# Triangulator-LM358.net
KiCad netlist of a schematic drawn in EAGLE
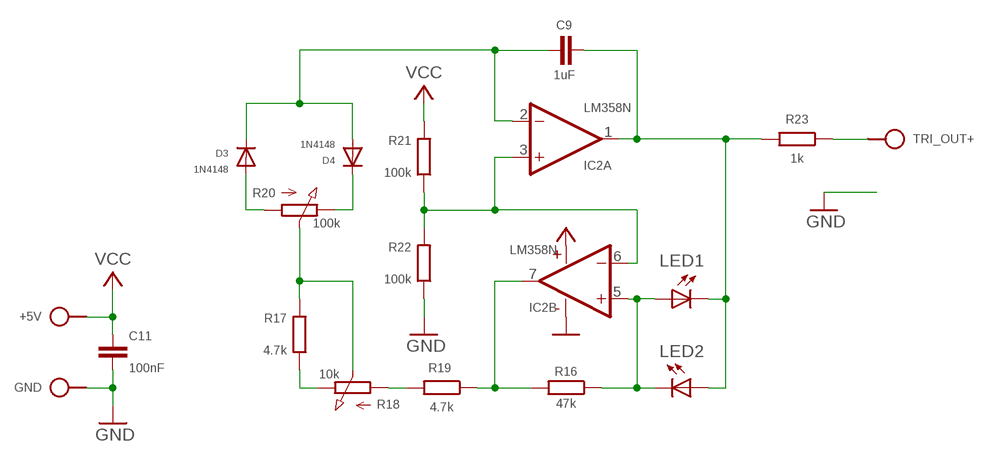
[diagram p0: schematic, sheet 1]

(export (version "E")
  (design (tool "Eeschema 10.0.6"))
  (components
    (comp (ref "+5V")
      (value "VCC")
      (footprint "eagle-import:SPAD")
      (libsource (lib "eagle-import") (part "SPAD"))
    )
    (comp (ref "C9")
      (value "1uF")
      (footprint "eagle-import:C050-020X036_V")
      (libsource (lib "eagle-import") (part "C050-020X036/V"))
    )
    (comp (ref "C11")
      (value "100nF")
      (footprint "eagle-import:C050-020X036")
      (libsource (lib "eagle-import") (part "C050-020X036"))
    )
    (comp (ref "D3")
      (value "1N4148")
      (footprint "eagle-import:DO34-5V")
      (libsource (lib "eagle-import") (part "1N414834-5V"))
    )
    (comp (ref "D4")
      (value "1N4148")
      (footprint "eagle-import:DO34-5V")
      (libsource (lib "eagle-import") (part "1N414834-5V"))
    )
    (comp (ref "GND")
      (value "GND")
      (footprint "eagle-import:SPAD")
      (libsource (lib "eagle-import") (part "SPAD"))
    )
    (comp (ref "IC2")
      (value "LM358N")
      (footprint "eagle-import:DIL08")
      (libsource (lib "eagle-import") (part "LM358N"))
    )
    (comp (ref "LED1")
      (value "LED3MM")
      (footprint "eagle-import:LED3MM")
      (libsource (lib "eagle-import") (part "LED3MM"))
    )
    (comp (ref "LED2")
      (value "LED3MM")
      (footprint "eagle-import:LED3MM")
      (libsource (lib "eagle-import") (part "LED3MM"))
    )
    (comp (ref "R16")
      (value "47k")
      (footprint "eagle-import:0202_7-V")
      (libsource (lib "eagle-import") (part "R0202/7-V"))
    )
    (comp (ref "R17")
      (value "4.7k")
      (footprint "eagle-import:0202_7")
      (libsource (lib "eagle-import") (part "R0202/7"))
    )
    (comp (ref "R18")
      (value "10k")
      (footprint "eagle-import:POT")
      (libsource (lib "eagle-import") (part "POT"))
    )
    (comp (ref "R19")
      (value "4.7k")
      (footprint "eagle-import:0202_7-V")
      (libsource (lib "eagle-import") (part "R0202/7-V"))
    )
    (comp (ref "R20")
      (value "100k")
      (footprint "eagle-import:POT")
      (libsource (lib "eagle-import") (part "POT"))
    )
    (comp (ref "R21")
      (value "100k")
      (footprint "eagle-import:0202_7-V")
      (libsource (lib "eagle-import") (part "R0202/7-V"))
    )
    (comp (ref "R22")
      (value "100k")
      (footprint "eagle-import:0202_7-V")
      (libsource (lib "eagle-import") (part "R0202/7-V"))
    )
    (comp (ref "R23")
      (value "1k")
      (footprint "eagle-import:0202_5")
      (libsource (lib "eagle-import") (part "R0202/5"))
    )
    (comp (ref "TRI_OUT+")
      (value "TRIANGLE")
      (footprint "eagle-import:SPAD")
      (libsource (lib "eagle-import") (part "SPAD"))
    )
  )
  (nets
    (net (code "1") (name "GND") (class "Default")
      (node (ref "C11") (pin "2") (pinfunction "2_2") (pintype "passive"))
      (node (ref "GND") (pin "1") (pinfunction "P$1_1") (pintype "bidirectional"))
      (node (ref "IC2") (pin "4") (pinfunction "V-_4") (pintype "power_in"))
      (node (ref "R22") (pin "1") (pinfunction "1_1") (pintype "passive"))
    )
    (net (code "2") (name "Net-(IC2A-+IN)") (class "Default")
      (node (ref "IC2") (pin "3") (pinfunction "+IN_3") (pintype "input"))
      (node (ref "IC2") (pin "6") (pinfunction "-IN_6") (pintype "input"))
      (node (ref "R21") (pin "1") (pinfunction "1_1") (pintype "passive"))
      (node (ref "R22") (pin "2") (pinfunction "2_2") (pintype "passive"))
    )
    (net (code "3") (name "Net-(IC2A--IN)") (class "Default")
      (node (ref "C9") (pin "1") (pinfunction "1_1") (pintype "passive"))
      (node (ref "D3") (pin "C") (pinfunction "C_C") (pintype "passive"))
      (node (ref "D4") (pin "A") (pinfunction "A_A") (pintype "passive"))
      (node (ref "IC2") (pin "2") (pinfunction "-IN_2") (pintype "input"))
    )
    (net (code "4") (name "Net-(IC2A-OUT)") (class "Default")
      (node (ref "C9") (pin "2") (pinfunction "2_2") (pintype "passive"))
      (node (ref "IC2") (pin "1") (pinfunction "OUT_1") (pintype "output"))
      (node (ref "LED1") (pin "K") (pinfunction "C_K") (pintype "passive"))
      (node (ref "LED2") (pin "A") (pinfunction "A_A") (pintype "passive"))
      (node (ref "R23") (pin "2") (pinfunction "2_2") (pintype "passive"))
    )
    (net (code "5") (name "Net-(IC2B-+IN)") (class "Default")
      (node (ref "IC2") (pin "5") (pinfunction "+IN_5") (pintype "input"))
      (node (ref "LED1") (pin "A") (pinfunction "A_A") (pintype "passive"))
      (node (ref "LED2") (pin "K") (pinfunction "C_K") (pintype "passive"))
      (node (ref "R16") (pin "1") (pinfunction "1_1") (pintype "passive"))
    )
    (net (code "6") (name "Net-(IC2B-OUT)") (class "Default")
      (node (ref "IC2") (pin "7") (pinfunction "OUT_7") (pintype "output"))
      (node (ref "R16") (pin "2") (pinfunction "2_2") (pintype "passive"))
      (node (ref "R19") (pin "1") (pinfunction "1_1") (pintype "passive"))
    )
    (net (code "7") (name "Net-(R18-A)") (class "Default")
      (node (ref "R18") (pin "1") (pinfunction "A_1") (pintype "passive"))
      (node (ref "R19") (pin "2") (pinfunction "2_2") (pintype "passive"))
    )
    (net (code "8") (name "Net-(R18-E)") (class "Default")
      (node (ref "R17") (pin "1") (pinfunction "1_1") (pintype "passive"))
      (node (ref "R18") (pin "3") (pinfunction "E_3") (pintype "passive"))
    )
    (net (code "9") (name "Net-(R18-S)") (class "Default")
      (node (ref "R17") (pin "2") (pinfunction "2_2") (pintype "passive"))
      (node (ref "R18") (pin "2") (pinfunction "S_2") (pintype "passive"))
      (node (ref "R20") (pin "2") (pinfunction "S_2") (pintype "passive"))
    )
    (net (code "10") (name "Net-(R20-A)") (class "Default")
      (node (ref "D3") (pin "A") (pinfunction "A_A") (pintype "passive"))
      (node (ref "R20") (pin "1") (pinfunction "A_1") (pintype "passive"))
    )
    (net (code "11") (name "Net-(R20-E)") (class "Default")
      (node (ref "D4") (pin "C") (pinfunction "C_C") (pintype "passive"))
      (node (ref "R20") (pin "3") (pinfunction "E_3") (pintype "passive"))
    )
    (net (code "12") (name "Net-(TRI_OUT+-P$1)") (class "Default")
      (node (ref "R23") (pin "1") (pinfunction "1_1") (pintype "passive"))
      (node (ref "TRI_OUT+") (pin "1") (pinfunction "P$1_1") (pintype "bidirectional"))
    )
    (net (code "13") (name "VCC") (class "Default")
      (node (ref "+5V") (pin "1") (pinfunction "P$1_1") (pintype "bidirectional"))
      (node (ref "C11") (pin "1") (pinfunction "1_1") (pintype "passive"))
      (node (ref "IC2") (pin "8") (pinfunction "V+_8") (pintype "power_in"))
      (node (ref "R21") (pin "2") (pinfunction "2_2") (pintype "passive"))
    )
  )
)
